# Sheet_MAGJACK.net
KiCad netlist of a schematic drawn in Altium Designer
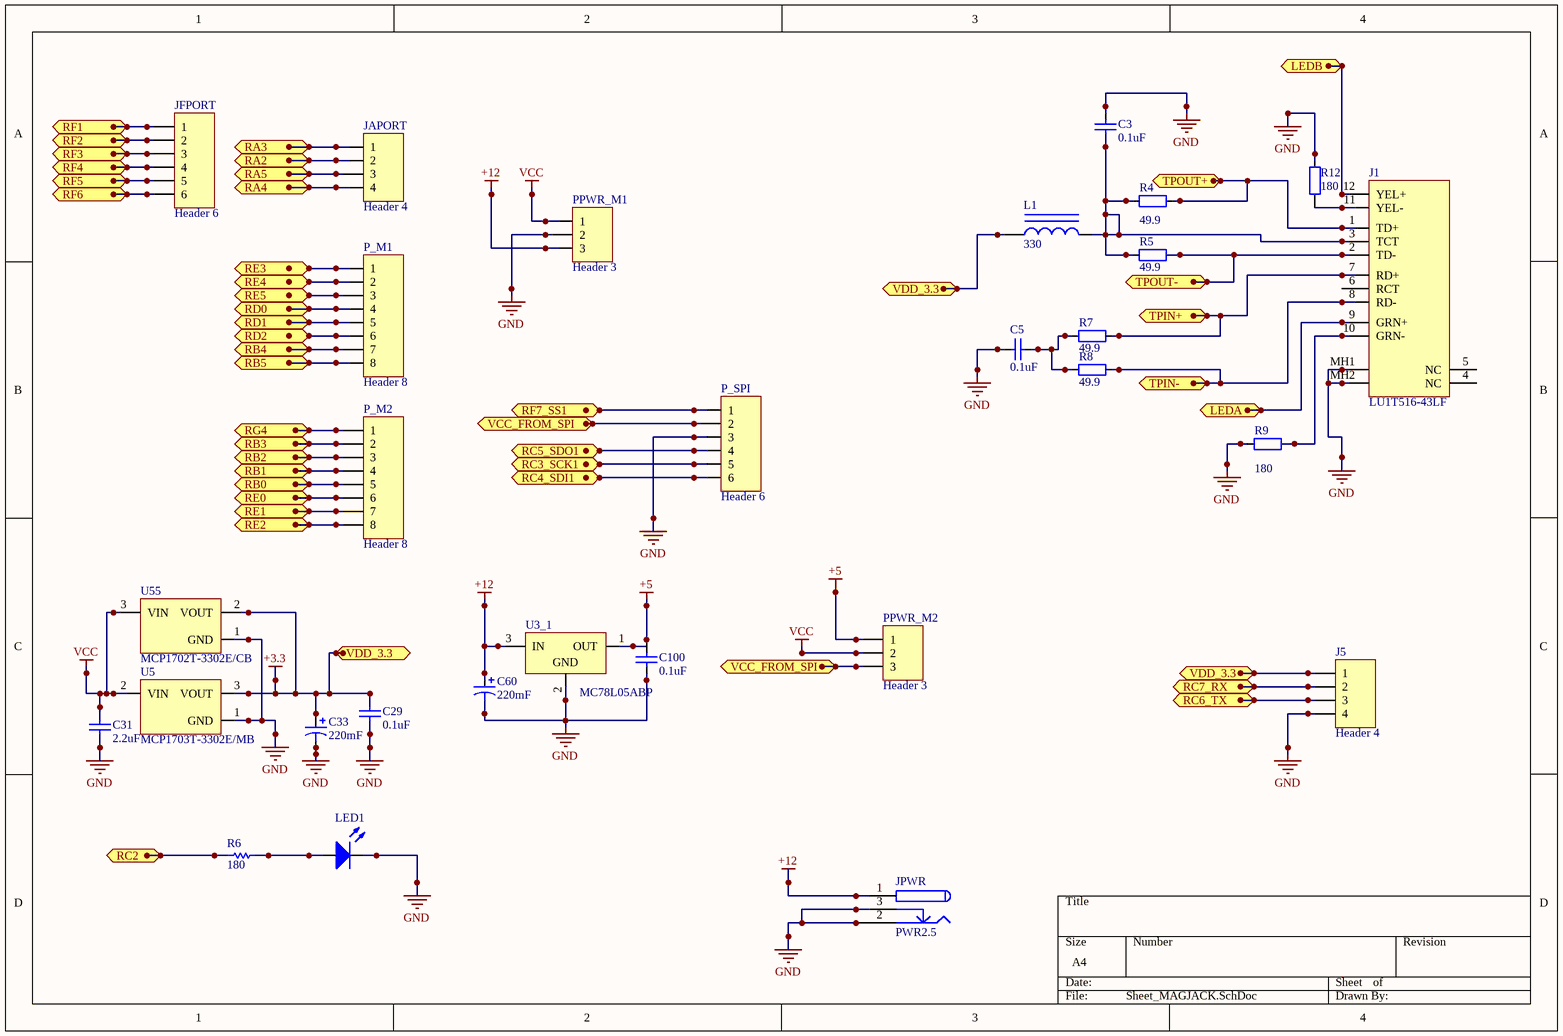
[diagram p0: Sheet_MAGJACK.SchDoc]

(export (version "E")
  (design (tool "Eeschema 10.0.6"))
  (components
    (comp (ref "C3")
      (value "0.1uF")
      (footprint "CAPC2012L")
      (description "Capacitor")
      (fields (field (name "PUBLISHER") "Altium Limited"))
      (libsource (lib "Miscellaneous Devices") (part "Cap"))
    )
    (comp (ref "C5")
      (value "0.1uF")
      (footprint "CAPC2012L")
      (description "Capacitor")
      (fields (field (name "PUBLISHER") "Altium Limited"))
      (libsource (lib "Miscellaneous Devices") (part "Cap"))
    )
    (comp (ref "C29")
      (value "0.1uF")
      (footprint "CAPC2012L")
      (description "Capacitor")
      (fields (field (name "PUBLISHER") "Altium Limited"))
      (libsource (lib "Miscellaneous Devices") (part "Cap"))
    )
    (comp (ref "C31")
      (value "2.2uF")
      (footprint "CAPC3216L")
      (description "Capacitor")
      (fields (field (name "PUBLISHER") "Altium Limited"))
      (libsource (lib "Miscellaneous Devices") (part "Cap"))
    )
    (comp (ref "C33")
      (value "220mF")
      (footprint "CAPPR5-10x12.5")
      (description "Polarized Capacitor (Radial)")
      (fields (field (name "PUBLISHER") "Altium Limited"))
      (libsource (lib "Miscellaneous Devices") (part "Cap Pol1"))
    )
    (comp (ref "C60")
      (value "220mF")
      (footprint "CAPPR5-10x12.5")
      (description "Polarized Capacitor (Radial)")
      (fields (field (name "PUBLISHER") "Altium Limited"))
      (libsource (lib "Miscellaneous Devices") (part "Cap Pol1"))
    )
    (comp (ref "C100")
      (value "0.1uF")
      (footprint "CAPC2012L")
      (description "Capacitor (Semiconductor SIM Model)")
      (fields (field (name "PUBLISHER") "Altium Limited"))
      (libsource (lib "Miscellaneous Devices") (part "Cap Semi"))
    )
    (comp (ref "J1")
      (value "LU1T516-43LF")
      (footprint "CON_RJ45_RA_LEDS")
      (libsource (lib "MagJack") (part "Component_1"))
    )
    (comp (ref "J5")
      (value "Header 4")
      (footprint "HDR1X4")
      (description "Header, 4-Pin")
      (fields (field (name "PUBLISHER") "Altium Limited"))
      (libsource (lib "Miscellaneous Connectors") (part "Header 4"))
    )
    (comp (ref "JAPORT")
      (value "Header 4")
      (footprint "HDR1X4")
      (description "Header, 4-Pin")
      (fields (field (name "PUBLISHER") "Altium Limited"))
      (libsource (lib "Miscellaneous Connectors") (part "Header 4"))
    )
    (comp (ref "JFPORT")
      (value "Header 6")
      (footprint "HDR1X6")
      (description "Header, 6-Pin")
      (fields (field (name "PUBLISHER") "Altium Limited"))
      (libsource (lib "Miscellaneous Connectors") (part "Header 6"))
    )
    (comp (ref "JPWR")
      (value "PWR2.5")
      (footprint "KLD-0202")
      (description "DC Power Jack, 2.5mm, KLD Series, PCB Mount")
      (fields (field (name "PUBLISHER") "Altium Limited"))
      (libsource (lib "PCB_4550") (part "PWR2.5"))
    )
    (comp (ref "L1")
      (value "330")
      (footprint "RESC2012L")
      (description "Magnetic-Core Inductor")
      (fields (field (name "PUBLISHER") "Altium Limited"))
      (libsource (lib "Miscellaneous Devices") (part "Inductor Iron"))
    )
    (comp (ref "LED1")
      (value "LED2")
      (footprint "CAPC2012L")
      (description "Typical RED, GREEN, YELLOW, AMBER GaAs LED")
      (fields (field (name "PUBLISHER") "Altium Limited"))
      (libsource (lib "Miscellaneous Devices") (part "LED2"))
    )
    (comp (ref "PPWR_M1")
      (value "Header 3")
      (footprint "HDR1X3")
      (description "Header, 3-Pin")
      (fields (field (name "PUBLISHER") "Altium Limited"))
      (libsource (lib "Miscellaneous Connectors") (part "Header 3"))
    )
    (comp (ref "PPWR_M2")
      (value "Header 3")
      (footprint "HDR1X3")
      (description "Header, 3-Pin")
      (fields (field (name "PUBLISHER") "Altium Limited"))
      (libsource (lib "Miscellaneous Connectors") (part "Header 3"))
    )
    (comp (ref "P_M1")
      (value "Header 8")
      (footprint "HDR1X8")
      (description "Header, 8-Pin")
      (fields (field (name "PUBLISHER") "Altium Limited"))
      (libsource (lib "Miscellaneous Connectors") (part "Header 8"))
    )
    (comp (ref "P_M2")
      (value "Header 8")
      (footprint "HDR1X8")
      (description "Header, 8-Pin")
      (fields (field (name "PUBLISHER") "Altium Limited"))
      (libsource (lib "Miscellaneous Connectors") (part "Header 8"))
    )
    (comp (ref "P_SPI")
      (value "Header 6")
      (footprint "HDR1X6")
      (description "Header, 6-Pin")
      (fields (field (name "PUBLISHER") "Altium Limited"))
      (libsource (lib "Miscellaneous Connectors") (part "Header 6"))
    )
    (comp (ref "R4")
      (value "49.9")
      (footprint "RESC2012L")
      (description "Resistor")
      (fields (field (name "PUBLISHER") "Altium Limited"))
      (libsource (lib "") (part "Res2_1"))
    )
    (comp (ref "R5")
      (value "49.9")
      (footprint "RESC2012L")
      (description "Resistor")
      (fields (field (name "PUBLISHER") "Altium Limited"))
      (libsource (lib "") (part "Res2_1"))
    )
    (comp (ref "R6")
      (value "180")
      (footprint "RESC2012L")
      (description "Semiconductor Resistor")
      (fields (field (name "PUBLISHER") "Altium Limited"))
      (libsource (lib "Miscellaneous Devices") (part "Res Semi"))
    )
    (comp (ref "R7")
      (value "49.9")
      (footprint "RESC2012L")
      (description "Resistor")
      (fields (field (name "PUBLISHER") "Altium Limited"))
      (libsource (lib "") (part "Res2_1"))
    )
    (comp (ref "R8")
      (value "49.9")
      (footprint "RESC2012L")
      (description "Resistor")
      (fields (field (name "PUBLISHER") "Altium Limited"))
      (libsource (lib "") (part "Res2_1"))
    )
    (comp (ref "R9")
      (value "180")
      (footprint "RESC2012L")
      (description "Resistor")
      (fields (field (name "PUBLISHER") "Altium Limited"))
      (libsource (lib "") (part "Res2_1"))
    )
    (comp (ref "R12")
      (value "180")
      (footprint "RESC2012L")
      (description "Resistor")
      (fields (field (name "PUBLISHER") "Altium Limited"))
      (libsource (lib "Miscellaneous Devices") (part "Res2"))
    )
    (comp (ref "U3_1")
      (value "MC78L05ABP")
      (footprint "29-04")
      (description "Three-Terminal Low Current Positive Voltage Regulator")
      (fields (field (name "PUBLISHER") "Altium Limited"))
      (libsource (lib "PCB_4550") (part "MC78L05ABP"))
    )
    (comp (ref "U5")
      (value "MCP1703T-3302E/MB")
      (footprint "SOT-89-MB3_N")
      (fields (field (name "PUBLISHER") "Altium Limited"))
      (libsource (lib "Microchip Power Mgt Line Regulator") (part "MCP1703T-3302E/MB"))
    )
    (comp (ref "U55")
      (value "MCP1702T-3302E/CB")
      (footprint "SOT-23A-CB3_N")
      (description "250 mA Low Quiescent Current LDO Regulator, 3-Pin SOT-23A, Extended Temperature, Tape and Reel")
      (fields (field (name "PUBLISHER") "Altium Limited"))
      (libsource (lib "Microchip Power Mgt Line Regulator") (part "MCP1702T-3302E/CB"))
    )
  )
  (nets
    (net (code "1") (name "+3.3") (class "Default")
      (node (ref "C29") (pin "2") (pinfunction "2_2") (pintype "passive"))
      (node (ref "C33") (pin "1") (pinfunction "1_1") (pintype "passive"))
      (node (ref "J5") (pin "1") (pinfunction "1_1") (pintype "passive"))
      (node (ref "L1") (pin "1") (pinfunction "1_1") (pintype "passive"))
      (node (ref "U5") (pin "3") (pinfunction "VOUT_3") (pintype "power_in"))
      (node (ref "U55") (pin "2") (pinfunction "VOUT_2") (pintype "power_in"))
    )
    (net (code "2") (name "+5") (class "Default")
      (node (ref "C100") (pin "2") (pinfunction "2_2") (pintype "passive"))
      (node (ref "PPWR_M2") (pin "1") (pinfunction "1_1") (pintype "passive"))
      (node (ref "U3_1") (pin "1") (pinfunction "OUT_1") (pintype "power_in"))
    )
    (net (code "3") (name "+12") (class "Default")
      (node (ref "C60") (pin "1") (pinfunction "1_1") (pintype "passive"))
      (node (ref "JPWR") (pin "1") (pinfunction "1_1") (pintype "power_in"))
      (node (ref "JPWR") (pin "1A") (pinfunction "1A_1A") (pintype "power_in"))
      (node (ref "JPWR") (pin "1B") (pinfunction "1B_1B") (pintype "power_in"))
      (node (ref "PPWR_M1") (pin "3") (pinfunction "3_3") (pintype "passive"))
      (node (ref "U3_1") (pin "3") (pinfunction "IN_3") (pintype "power_in"))
    )
    (net (code "4") (name "/LEDA") (class "Default")
      (node (ref "J1") (pin "9") (pinfunction "GRN+_9") (pintype "passive"))
    )
    (net (code "5") (name "/LEDB") (class "Default")
      (node (ref "J1") (pin "12") (pinfunction "YEL+_12") (pintype "passive"))
    )
    (net (code "6") (name "/RA2") (class "Default")
      (node (ref "JAPORT") (pin "2") (pinfunction "2_2") (pintype "passive"))
    )
    (net (code "7") (name "/RA3") (class "Default")
      (node (ref "JAPORT") (pin "1") (pinfunction "1_1") (pintype "passive"))
    )
    (net (code "8") (name "/RA4") (class "Default")
      (node (ref "JAPORT") (pin "4") (pinfunction "4_4") (pintype "passive"))
    )
    (net (code "9") (name "/RA5") (class "Default")
      (node (ref "JAPORT") (pin "3") (pinfunction "3_3") (pintype "passive"))
    )
    (net (code "10") (name "/RB0") (class "Default")
      (node (ref "P_M2") (pin "5") (pinfunction "5_5") (pintype "passive"))
    )
    (net (code "11") (name "/RB1") (class "Default")
      (node (ref "P_M2") (pin "4") (pinfunction "4_4") (pintype "passive"))
    )
    (net (code "12") (name "/RB2") (class "Default")
      (node (ref "P_M2") (pin "3") (pinfunction "3_3") (pintype "passive"))
    )
    (net (code "13") (name "/RB3") (class "Default")
      (node (ref "P_M2") (pin "2") (pinfunction "2_2") (pintype "passive"))
    )
    (net (code "14") (name "/RB4") (class "Default")
      (node (ref "P_M1") (pin "7") (pinfunction "7_7") (pintype "passive"))
    )
    (net (code "15") (name "/RB5") (class "Default")
      (node (ref "P_M1") (pin "8") (pinfunction "8_8") (pintype "passive"))
    )
    (net (code "16") (name "/RC2") (class "Default")
      (node (ref "R6") (pin "1") (pinfunction "1_1") (pintype "passive"))
    )
    (net (code "17") (name "/RC3_SCK1") (class "Default")
      (node (ref "P_SPI") (pin "5") (pinfunction "5_5") (pintype "passive"))
    )
    (net (code "18") (name "/RC4_SDI1") (class "Default")
      (node (ref "P_SPI") (pin "6") (pinfunction "6_6") (pintype "passive"))
    )
    (net (code "19") (name "/RC5_SDO1") (class "Default")
      (node (ref "P_SPI") (pin "4") (pinfunction "4_4") (pintype "passive"))
    )
    (net (code "20") (name "/RC6_TX") (class "Default")
      (node (ref "J5") (pin "3") (pinfunction "3_3") (pintype "passive"))
    )
    (net (code "21") (name "/RC7_RX") (class "Default")
      (node (ref "J5") (pin "2") (pinfunction "2_2") (pintype "passive"))
    )
    (net (code "22") (name "/RD0") (class "Default")
      (node (ref "P_M1") (pin "4") (pinfunction "4_4") (pintype "passive"))
    )
    (net (code "23") (name "/RD1") (class "Default")
      (node (ref "P_M1") (pin "5") (pinfunction "5_5") (pintype "passive"))
    )
    (net (code "24") (name "/RD2") (class "Default")
      (node (ref "P_M1") (pin "6") (pinfunction "6_6") (pintype "passive"))
    )
    (net (code "25") (name "/RE0") (class "Default")
      (node (ref "P_M2") (pin "6") (pinfunction "6_6") (pintype "passive"))
    )
    (net (code "26") (name "/RE1") (class "Default")
      (node (ref "P_M2") (pin "7") (pinfunction "7_7") (pintype "passive"))
    )
    (net (code "27") (name "/RE2") (class "Default")
      (node (ref "P_M2") (pin "8") (pinfunction "8_8") (pintype "passive"))
    )
    (net (code "28") (name "/RE3") (class "Default")
      (node (ref "P_M1") (pin "1") (pinfunction "1_1") (pintype "passive"))
    )
    (net (code "29") (name "/RE4") (class "Default")
      (node (ref "P_M1") (pin "2") (pinfunction "2_2") (pintype "passive"))
    )
    (net (code "30") (name "/RE5") (class "Default")
      (node (ref "P_M1") (pin "3") (pinfunction "3_3") (pintype "passive"))
    )
    (net (code "31") (name "/RF1") (class "Default")
      (node (ref "JFPORT") (pin "1") (pinfunction "1_1") (pintype "passive"))
    )
    (net (code "32") (name "/RF2") (class "Default")
      (node (ref "JFPORT") (pin "2") (pinfunction "2_2") (pintype "passive"))
    )
    (net (code "33") (name "/RF3") (class "Default")
      (node (ref "JFPORT") (pin "3") (pinfunction "3_3") (pintype "passive"))
    )
    (net (code "34") (name "/RF4") (class "Default")
      (node (ref "JFPORT") (pin "4") (pinfunction "4_4") (pintype "passive"))
    )
    (net (code "35") (name "/RF5") (class "Default")
      (node (ref "JFPORT") (pin "5") (pinfunction "5_5") (pintype "passive"))
    )
    (net (code "36") (name "/RF6") (class "Default")
      (node (ref "JFPORT") (pin "6") (pinfunction "6_6") (pintype "passive"))
    )
    (net (code "37") (name "/RF7_SS1") (class "Default")
      (node (ref "P_SPI") (pin "1") (pinfunction "1_1") (pintype "passive"))
    )
    (net (code "38") (name "/RG4") (class "Default")
      (node (ref "P_M2") (pin "1") (pinfunction "1_1") (pintype "passive"))
    )
    (net (code "39") (name "/TPIN+") (class "Default")
      (node (ref "J1") (pin "7") (pinfunction "RD+_7") (pintype "passive"))
      (node (ref "R7") (pin "2") (pinfunction "2_2") (pintype "passive"))
    )
    (net (code "40") (name "/TPIN-") (class "Default")
      (node (ref "J1") (pin "8") (pinfunction "RD-_8") (pintype "passive"))
      (node (ref "R8") (pin "2") (pinfunction "2_2") (pintype "passive"))
    )
    (net (code "41") (name "/TPOUT+") (class "Default")
      (node (ref "J1") (pin "1") (pinfunction "TD+_1") (pintype "passive"))
      (node (ref "R4") (pin "2") (pinfunction "2_2") (pintype "passive"))
    )
    (net (code "42") (name "/TPOUT-") (class "Default")
      (node (ref "J1") (pin "2") (pinfunction "TD-_2") (pintype "passive"))
      (node (ref "R5") (pin "2") (pinfunction "2_2") (pintype "passive"))
    )
    (net (code "43") (name "/VCC_FROM_SPI") (class "Default")
      (node (ref "PPWR_M2") (pin "3") (pinfunction "3_3") (pintype "passive"))
      (node (ref "P_SPI") (pin "2") (pinfunction "2_2") (pintype "passive"))
    )
    (net (code "44") (name "GND") (class "Default")
      (node (ref "C100") (pin "1") (pinfunction "1_1") (pintype "passive"))
      (node (ref "C29") (pin "1") (pinfunction "1_1") (pintype "passive"))
      (node (ref "C3") (pin "2") (pinfunction "2_2") (pintype "passive"))
      (node (ref "C31") (pin "1") (pinfunction "1_1") (pintype "passive"))
      (node (ref "C33") (pin "2") (pinfunction "2_2") (pintype "passive"))
      (node (ref "C5") (pin "1") (pinfunction "1_1") (pintype "passive"))
      (node (ref "C60") (pin "2") (pinfunction "2_2") (pintype "passive"))
      (node (ref "J1") (pin "MH1") (pinfunction "MH1_MH1") (pintype "passive"))
      (node (ref "J1") (pin "MH2") (pinfunction "MH2_MH2") (pintype "passive"))
      (node (ref "J5") (pin "4") (pinfunction "4_4") (pintype "passive"))
      (node (ref "JPWR") (pin "2") (pinfunction "2_2") (pintype "power_in"))
      (node (ref "JPWR") (pin "2A") (pinfunction "2A_2A") (pintype "power_in"))
      (node (ref "JPWR") (pin "2B") (pinfunction "2B_2B") (pintype "power_in"))
      (node (ref "JPWR") (pin "3") (pinfunction "3_3") (pintype "power_in"))
      (node (ref "JPWR") (pin "3A") (pinfunction "3A_3A") (pintype "power_in"))
      (node (ref "JPWR") (pin "3B") (pinfunction "3B_3B") (pintype "power_in"))
      (node (ref "LED1") (pin "2") (pinfunction "K_2") (pintype "passive"))
      (node (ref "PPWR_M1") (pin "2") (pinfunction "2_2") (pintype "passive"))
      (node (ref "P_SPI") (pin "3") (pinfunction "3_3") (pintype "passive"))
      (node (ref "R12") (pin "2") (pinfunction "2_2") (pintype "passive"))
      (node (ref "R9") (pin "1") (pinfunction "1_1") (pintype "passive"))
      (node (ref "U3_1") (pin "2") (pinfunction "GND_2") (pintype "power_in"))
      (node (ref "U5") (pin "1") (pinfunction "GND_1") (pintype "power_in"))
      (node (ref "U55") (pin "1") (pinfunction "GND_1") (pintype "power_in"))
    )
    (net (code "45") (name "Net-(C5-Pad2)") (class "Default")
      (node (ref "C5") (pin "2") (pinfunction "2_2") (pintype "passive"))
      (node (ref "R7") (pin "1") (pinfunction "1_1") (pintype "passive"))
      (node (ref "R8") (pin "1") (pinfunction "1_1") (pintype "passive"))
    )
    (net (code "46") (name "Net-(J1-GRN-)") (class "Default")
      (node (ref "J1") (pin "10") (pinfunction "GRN-_10") (pintype "passive"))
      (node (ref "R9") (pin "2") (pinfunction "2_2") (pintype "passive"))
    )
    (net (code "47") (name "Net-(J1-TCT)") (class "Default")
      (node (ref "C3") (pin "1") (pinfunction "1_1") (pintype "passive"))
      (node (ref "J1") (pin "3") (pinfunction "TCT_3") (pintype "passive"))
      (node (ref "L1") (pin "2") (pinfunction "2_2") (pintype "passive"))
      (node (ref "R4") (pin "1") (pinfunction "1_1") (pintype "passive"))
      (node (ref "R5") (pin "1") (pinfunction "1_1") (pintype "passive"))
    )
    (net (code "48") (name "Net-(J1-YEL-)") (class "Default")
      (node (ref "J1") (pin "11") (pinfunction "YEL-_11") (pintype "passive"))
      (node (ref "R12") (pin "1") (pinfunction "1_1") (pintype "passive"))
    )
    (net (code "49") (name "Net-(LED1-A)") (class "Default")
      (node (ref "LED1") (pin "1") (pinfunction "A_1") (pintype "passive"))
      (node (ref "R6") (pin "2") (pinfunction "2_2") (pintype "passive"))
    )
    (net (code "50") (name "VCC") (class "Default")
      (node (ref "C31") (pin "2") (pinfunction "2_2") (pintype "passive"))
      (node (ref "PPWR_M1") (pin "1") (pinfunction "1_1") (pintype "passive"))
      (node (ref "PPWR_M2") (pin "2") (pinfunction "2_2") (pintype "passive"))
      (node (ref "U5") (pin "2") (pinfunction "VIN_2") (pintype "power_in"))
      (node (ref "U55") (pin "3") (pinfunction "VIN_3") (pintype "power_in"))
    )
    (net (code "51") (name "unconnected-(J1-NC-Pad4)") (class "Default")
      (node (ref "J1") (pin "4") (pinfunction "NC_4") (pintype "passive"))
    )
    (net (code "52") (name "unconnected-(J1-NC-Pad5)") (class "Default")
      (node (ref "J1") (pin "5") (pinfunction "NC_5") (pintype "passive"))
    )
    (net (code "53") (name "unconnected-(J1-RCT-Pad6)") (class "Default")
      (node (ref "J1") (pin "6") (pinfunction "RCT_6") (pintype "passive"))
    )
  )
)
